# Plataforma_soldadora.net
KiCad netlist of a schematic drawn in EAGLE
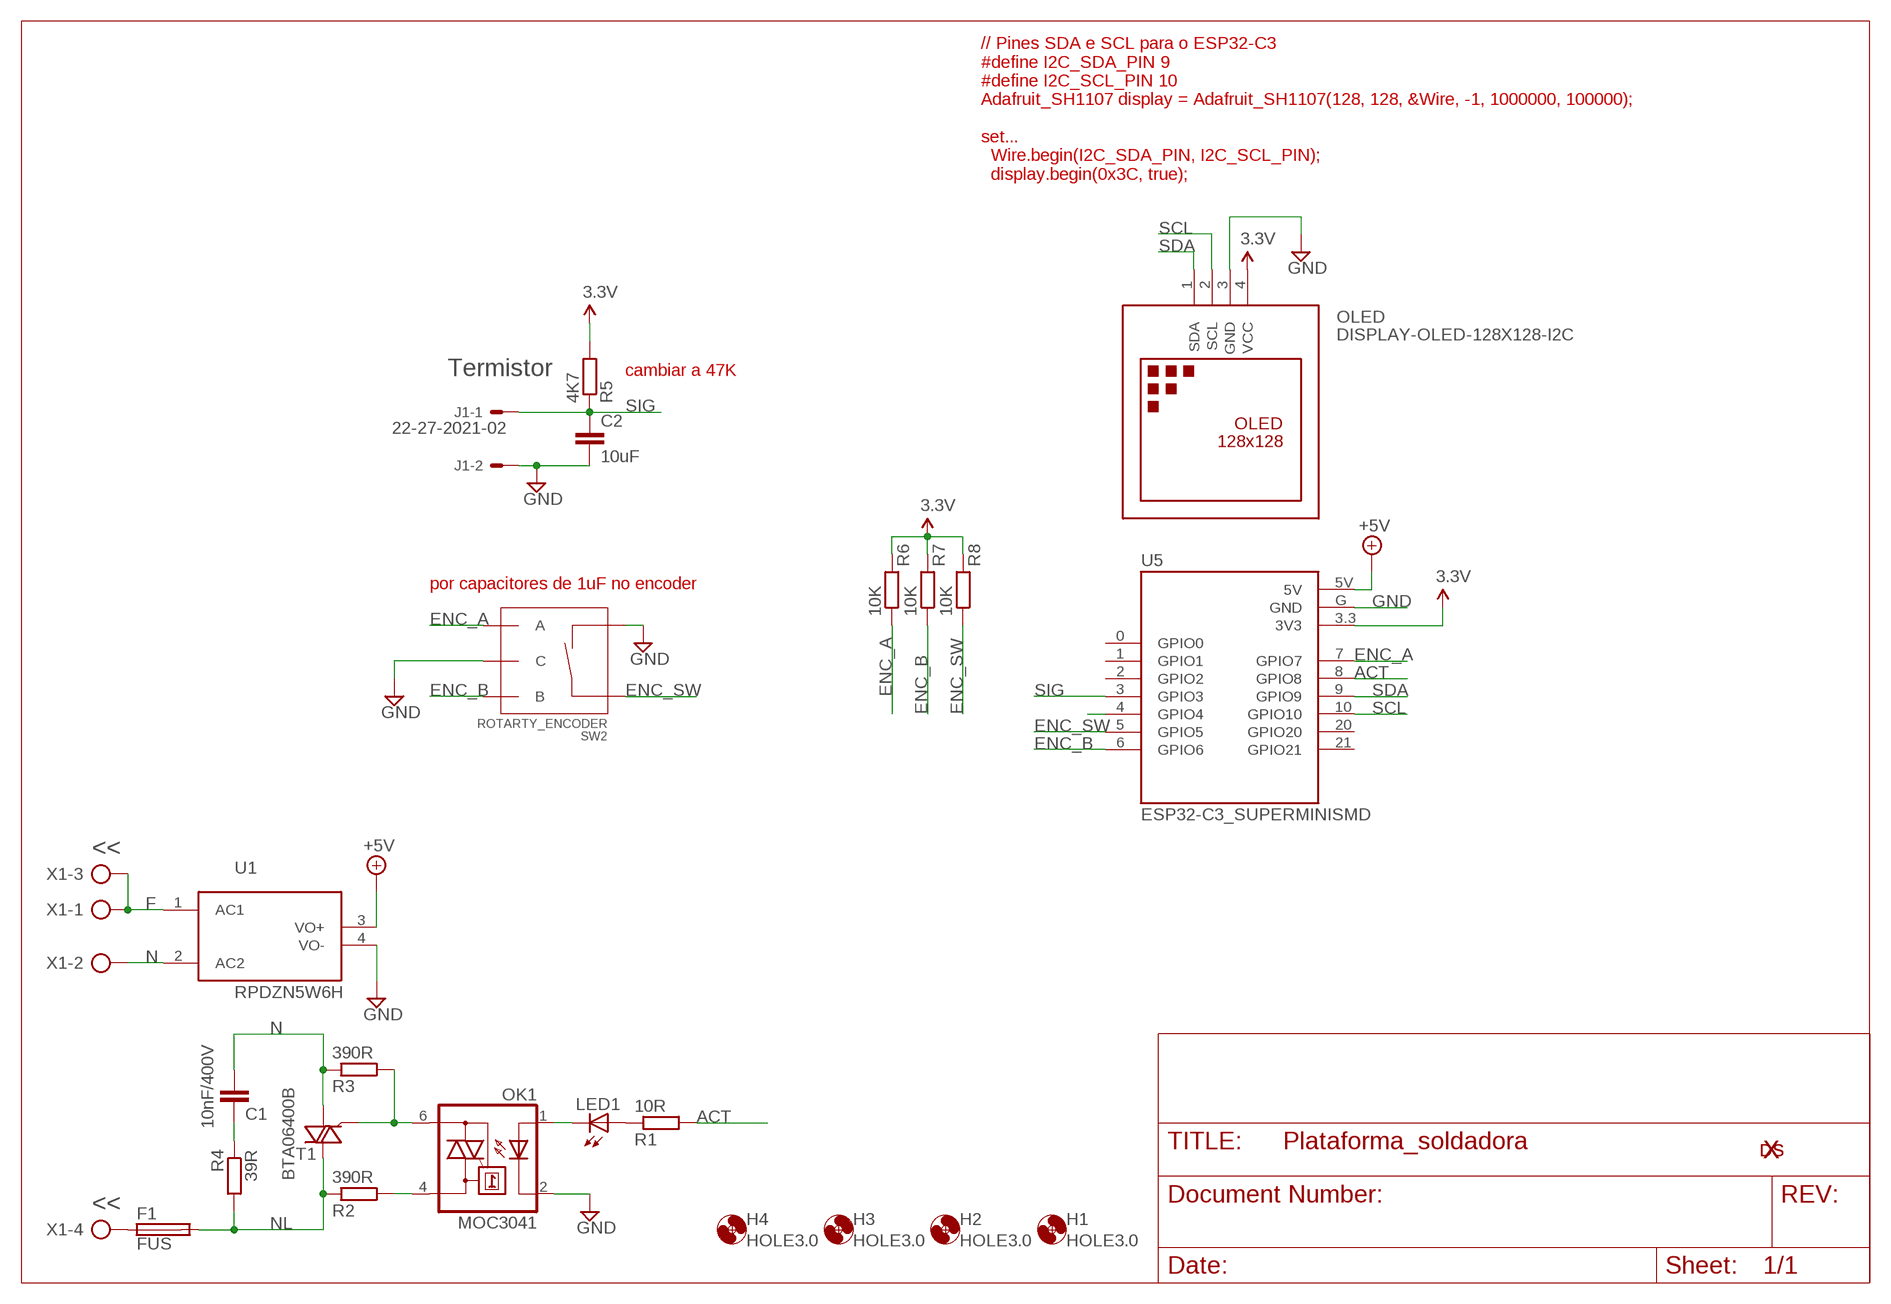
[diagram p0: schematic, sheet 1]

(export (version "E")
  (design (tool "Eeschema 10.0.6"))
  (components
    (comp (ref "C1")
      (value "10nF/400V")
      (footprint "eagle-import:C075-042X103")
      (libsource (lib "eagle-import") (part "C-EU075-042X103"))
    )
    (comp (ref "C2")
      (value "10uF")
      (footprint "eagle-import:C1206K")
      (libsource (lib "eagle-import") (part "C-EUC1206K"))
    )
    (comp (ref "F1")
      (value "FUS")
      (footprint "eagle-import:TE5")
      (libsource (lib "eagle-import") (part "FUSETE5"))
    )
    (comp (ref "H1")
      (value "HOLE3.0")
      (footprint "eagle-import:HOLES_3,0")
      (libsource (lib "eagle-import") (part "HOLES_MOUNT-HOLE3.0"))
    )
    (comp (ref "H2")
      (value "HOLE3.0")
      (footprint "eagle-import:HOLES_3,0")
      (libsource (lib "eagle-import") (part "HOLES_MOUNT-HOLE3.0"))
    )
    (comp (ref "H3")
      (value "HOLE3.0")
      (footprint "eagle-import:HOLES_3,0")
      (libsource (lib "eagle-import") (part "HOLES_MOUNT-HOLE3.0"))
    )
    (comp (ref "H4")
      (value "HOLE3.0")
      (footprint "eagle-import:HOLES_3,0")
      (libsource (lib "eagle-import") (part "HOLES_MOUNT-HOLE3.0"))
    )
    (comp (ref "J1")
      (value "22-27-2021-02")
      (footprint "eagle-import:6410-02")
      (libsource (lib "eagle-import") (part "22-?-0227-2021"))
    )
    (comp (ref "LED1")
      (value "LED3MM")
      (footprint "eagle-import:LED3MM")
      (libsource (lib "eagle-import") (part "LED3MM"))
    )
    (comp (ref "OK1")
      (value "MOC3041")
      (footprint "eagle-import:DIL06")
      (fields (field (name "MF") "VISHAY/TELEFUNKEN") (field (name "MPN") "IL410"))
      (libsource (lib "eagle-import") (part "IL410"))
    )
    (comp (ref "OLED")
      (value "DISPLAY-OLED-128X128-I2C")
      (footprint "eagle-import:DISPLAY-OLED-128X128-I2C")
      (libsource (lib "eagle-import") (part "DISPLAY-OLED-128X128-I2C"))
    )
    (comp (ref "R1")
      (value "10R")
      (footprint "eagle-import:R0603")
      (libsource (lib "eagle-import") (part "R-EU_R0603"))
    )
    (comp (ref "R2")
      (value "390R")
      (footprint "eagle-import:0204_7")
      (libsource (lib "eagle-import") (part "R-EU_0204/7"))
    )
    (comp (ref "R3")
      (value "390R")
      (footprint "eagle-import:0204_7")
      (libsource (lib "eagle-import") (part "R-EU_0204/7"))
    )
    (comp (ref "R4")
      (value "39R")
      (footprint "eagle-import:0204_7")
      (libsource (lib "eagle-import") (part "R-EU_0204/7"))
    )
    (comp (ref "R5")
      (value "4K7")
      (footprint "eagle-import:R0603")
      (libsource (lib "eagle-import") (part "R-EU_R0603"))
    )
    (comp (ref "R6")
      (value "10K")
      (footprint "eagle-import:R0603")
      (libsource (lib "eagle-import") (part "R-EU_R0603"))
    )
    (comp (ref "R7")
      (value "10K")
      (footprint "eagle-import:R0603")
      (libsource (lib "eagle-import") (part "R-EU_R0603"))
    )
    (comp (ref "R8")
      (value "10K")
      (footprint "eagle-import:R0603")
      (libsource (lib "eagle-import") (part "R-EU_R0603"))
    )
    (comp (ref "SW2")
      (value "ROTARTY_ENCODER")
      (footprint "eagle-import:ROTARY_ENC_PLAIN")
      (libsource (lib "eagle-import") (part "ROTARTY_ENCODER"))
    )
    (comp (ref "T1")
      (value "BTA06400B")
      (footprint "eagle-import:TO220AB")
      (libsource (lib "eagle-import") (part "BT136"))
    )
    (comp (ref "U$2")
      (value "XDESIG_XDESIG5MM")
      (footprint "eagle-import:XDESIG_XDESIG_CU")
      (libsource (lib "eagle-import") (part "XDESIG_XDESIG5MM"))
    )
    (comp (ref "U$3")
      (value "XDESIG_XDESIG21")
      (footprint "eagle-import:XDESIG_XDESIG")
      (libsource (lib "eagle-import") (part "XDESIG_XDESIG21"))
    )
    (comp (ref "U1")
      (value "RPDZN5W6H")
      (footprint "eagle-import:RPDZN5W6H")
      (libsource (lib "eagle-import") (part "RPDZN5W6H"))
    )
    (comp (ref "U5")
      (value "ESP32-C3_SUPERMINISMD")
      (footprint "eagle-import:MODULE_ESP-C3_SUPERMINI_SMD")
      (libsource (lib "eagle-import") (part "ESP32-C3_SUPERMINISMD"))
    )
    (comp (ref "X1")
      (value "AK500/4-H")
      (footprint "eagle-import:AK500_4-H")
      (libsource (lib "eagle-import") (part "AK500/4-H"))
    )
  )
  (nets
    (net (code "1") (name "+5V") (class "Default")
      (node (ref "U1") (pin "3") (pinfunction "VO+_3") (pintype "bidirectional"))
      (node (ref "U5") (pin "5V") (pinfunction "5V_5V") (pintype "power_in"))
    )
    (net (code "2") (name "/ACT") (class "Default")
      (node (ref "R1") (pin "2") (pinfunction "2_2") (pintype "passive"))
      (node (ref "U5") (pin "8") (pinfunction "GPIO8_8") (pintype "bidirectional"))
    )
    (net (code "3") (name "/ENC_A") (class "Default")
      (node (ref "R6") (pin "1") (pinfunction "1_1") (pintype "passive"))
      (node (ref "SW2") (pin "A") (pinfunction "A_A") (pintype "bidirectional"))
      (node (ref "U5") (pin "7") (pinfunction "GPIO7_7") (pintype "bidirectional"))
    )
    (net (code "4") (name "/ENC_B") (class "Default")
      (node (ref "R7") (pin "1") (pinfunction "1_1") (pintype "passive"))
      (node (ref "SW2") (pin "B") (pinfunction "B_B") (pintype "bidirectional"))
      (node (ref "U5") (pin "6") (pinfunction "GPIO6_6") (pintype "bidirectional"))
    )
    (net (code "5") (name "/ENC_SW") (class "Default")
      (node (ref "R8") (pin "1") (pinfunction "1_1") (pintype "passive"))
      (node (ref "SW2") (pin "SW+") (pinfunction "SW+_SW+") (pintype "bidirectional"))
      (node (ref "U5") (pin "5") (pinfunction "GPIO5_5") (pintype "bidirectional"))
    )
    (net (code "6") (name "/F") (class "Default")
      (node (ref "U1") (pin "1") (pinfunction "AC1_1") (pintype "bidirectional"))
      (node (ref "X1") (pin "1") (pinfunction "KL_1") (pintype "passive"))
      (node (ref "X1") (pin "3") (pinfunction "KL_3") (pintype "passive"))
    )
    (net (code "7") (name "/N") (class "Default")
      (node (ref "C1") (pin "2") (pinfunction "2_2") (pintype "passive"))
      (node (ref "R3") (pin "1") (pinfunction "1_1") (pintype "passive"))
      (node (ref "T1") (pin "1") (pinfunction "A1_1") (pintype "passive"))
      (node (ref "U1") (pin "2") (pinfunction "AC2_2") (pintype "bidirectional"))
      (node (ref "X1") (pin "2") (pinfunction "KL_2") (pintype "passive"))
    )
    (net (code "8") (name "/NL") (class "Default")
      (node (ref "F1") (pin "2") (pinfunction "2_2") (pintype "passive"))
      (node (ref "R2") (pin "1") (pinfunction "1_1") (pintype "passive"))
      (node (ref "R4") (pin "2") (pinfunction "2_2") (pintype "passive"))
      (node (ref "T1") (pin "2") (pinfunction "A2_2") (pintype "passive"))
    )
    (net (code "9") (name "/SCL") (class "Default")
      (node (ref "OLED") (pin "2") (pinfunction "SCL_2") (pintype "bidirectional"))
      (node (ref "U5") (pin "10") (pinfunction "GPIO10_10") (pintype "bidirectional"))
    )
    (net (code "10") (name "/SDA") (class "Default")
      (node (ref "OLED") (pin "1") (pinfunction "SDA_1") (pintype "bidirectional"))
      (node (ref "U5") (pin "9") (pinfunction "GPIO9_9") (pintype "bidirectional"))
    )
    (net (code "11") (name "/SIG") (class "Default")
      (node (ref "C2") (pin "1") (pinfunction "1_1") (pintype "passive"))
      (node (ref "J1") (pin "1") (pinfunction "S_1") (pintype "passive"))
      (node (ref "R5") (pin "1") (pinfunction "1_1") (pintype "passive"))
      (node (ref "U5") (pin "3") (pinfunction "GPIO3_3") (pintype "bidirectional"))
    )
    (net (code "12") (name "3.3V") (class "Default")
      (node (ref "OLED") (pin "4") (pinfunction "VCC_4") (pintype "power_in"))
      (node (ref "R5") (pin "2") (pinfunction "2_2") (pintype "passive"))
      (node (ref "R6") (pin "2") (pinfunction "2_2") (pintype "passive"))
      (node (ref "R7") (pin "2") (pinfunction "2_2") (pintype "passive"))
      (node (ref "R8") (pin "2") (pinfunction "2_2") (pintype "passive"))
      (node (ref "U5") (pin "3.3") (pinfunction "3V3_3.3") (pintype "power_in"))
    )
    (net (code "13") (name "GND") (class "Default")
      (node (ref "C2") (pin "2") (pinfunction "2_2") (pintype "passive"))
      (node (ref "J1") (pin "2") (pinfunction "S_2") (pintype "passive"))
      (node (ref "OK1") (pin "2") (pinfunction "C_2") (pintype "passive"))
      (node (ref "OLED") (pin "3") (pinfunction "GND_3") (pintype "power_in"))
      (node (ref "SW2") (pin "C") (pinfunction "C_C") (pintype "bidirectional"))
      (node (ref "SW2") (pin "SW-") (pinfunction "SW-_SW-") (pintype "bidirectional"))
      (node (ref "U1") (pin "4") (pinfunction "VO-_4") (pintype "bidirectional"))
      (node (ref "U5") (pin "G") (pinfunction "GND_G") (pintype "power_in"))
    )
    (net (code "14") (name "Net-(C1-Pad1)") (class "Default")
      (node (ref "C1") (pin "1") (pinfunction "1_1") (pintype "passive"))
      (node (ref "R4") (pin "1") (pinfunction "1_1") (pintype "passive"))
    )
    (net (code "15") (name "Net-(LED1-C)") (class "Default")
      (node (ref "LED1") (pin "K") (pinfunction "C_K") (pintype "passive"))
      (node (ref "OK1") (pin "1") (pinfunction "A_1") (pintype "passive"))
    )
    (net (code "16") (name "Net-(LED1-PadA)") (class "Default")
      (node (ref "LED1") (pin "A") (pinfunction "A_A") (pintype "passive"))
      (node (ref "R1") (pin "1") (pinfunction "1_1") (pintype "passive"))
    )
    (net (code "17") (name "Net-(OK1-A1)") (class "Default")
      (node (ref "OK1") (pin "4") (pinfunction "A1_4") (pintype "passive"))
      (node (ref "R2") (pin "2") (pinfunction "2_2") (pintype "passive"))
    )
    (net (code "18") (name "Net-(OK1-A2)") (class "Default")
      (node (ref "OK1") (pin "6") (pinfunction "A2_6") (pintype "passive"))
      (node (ref "R3") (pin "2") (pinfunction "2_2") (pintype "passive"))
      (node (ref "T1") (pin "3") (pinfunction "G_3") (pintype "passive"))
    )
    (net (code "19") (name "Net-(X1D-KL)") (class "Default")
      (node (ref "F1") (pin "1") (pinfunction "1_1") (pintype "passive"))
      (node (ref "X1") (pin "4") (pinfunction "KL_4") (pintype "passive"))
    )
    (net (code "20") (name "unconnected-(U5-GPIO0-Pad0)") (class "Default")
      (node (ref "U5") (pin "0") (pinfunction "GPIO0_0") (pintype "bidirectional"))
    )
    (net (code "21") (name "unconnected-(U5-GPIO1-Pad1)") (class "Default")
      (node (ref "U5") (pin "1") (pinfunction "GPIO1_1") (pintype "bidirectional"))
    )
    (net (code "22") (name "unconnected-(U5-GPIO2-Pad2)") (class "Default")
      (node (ref "U5") (pin "2") (pinfunction "GPIO2_2") (pintype "bidirectional"))
    )
    (net (code "23") (name "unconnected-(U5-GPIO4-Pad4)") (class "Default")
      (node (ref "U5") (pin "4") (pinfunction "GPIO4_4") (pintype "bidirectional"))
    )
    (net (code "24") (name "unconnected-(U5-GPIO20-Pad20)") (class "Default")
      (node (ref "U5") (pin "20") (pinfunction "GPIO20_20") (pintype "bidirectional"))
    )
    (net (code "25") (name "unconnected-(U5-GPIO21-Pad21)") (class "Default")
      (node (ref "U5") (pin "21") (pinfunction "GPIO21_21") (pintype "bidirectional"))
    )
  )
)
